# CoproMKII_Connectors.net
KiCad netlist of a schematic drawn in Altium Designer
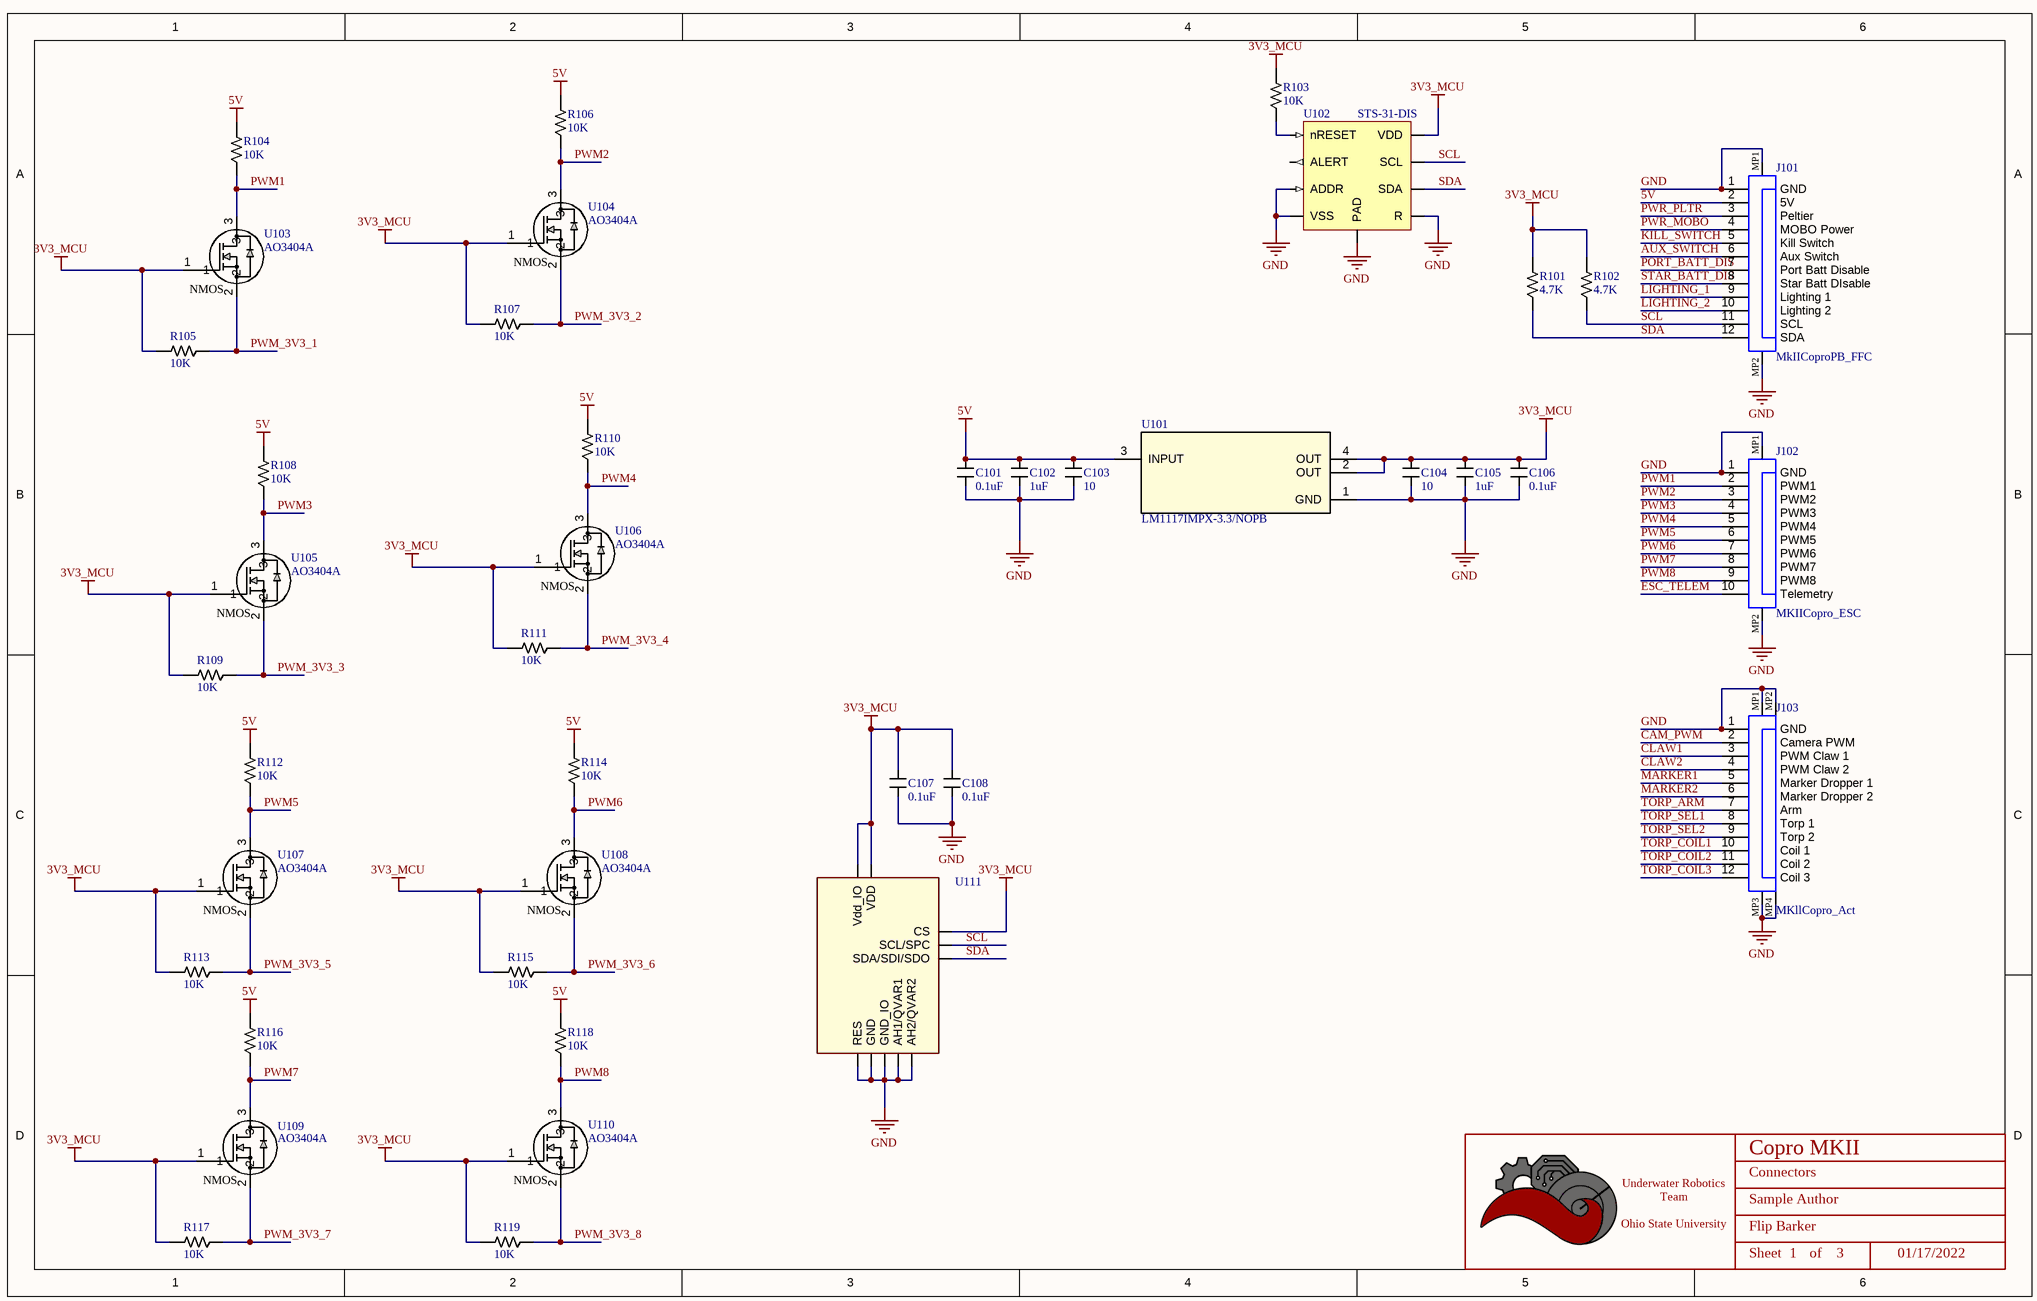
[diagram p0: CoproMKII_Connectors.SchDoc]

(export (version "E")
  (design (tool "Eeschema 10.0.6"))
  (components
    (comp (ref "C101")
      (value "0.1uF")
      (footprint "CAPACITOR_0603")
      (description "Cap 100nF 6.3V +/-10%\r\nCeramic 0603")
      (fields
        (field (name "TOLERANCE") "+/- 10%")
        (field (name "VOLTAGE") "6.3V")
        (field (name "MADE BY") "Flip B")
      )
      (libsource (lib "Capacitors") (part "CAPACITOR_0.1uF_0603"))
    )
    (comp (ref "C102")
      (value "1uF")
      (footprint "CAPACITOR_0603")
      (description "Cap 1uF 16V +/-10%\r\nCeramic 0603")
      (fields
        (field (name "TOLERANCE") "+/- 10%")
        (field (name "VOLTAGE") "16V")
        (field (name "MADE BY") "Flip B")
      )
      (libsource (lib "Capacitors") (part "CAPACITOR_1uF_0603"))
    )
    (comp (ref "C103")
      (value "10uF Ceramic 6.3V")
      (footprint "CAPACITOR_0603")
      (description "Cap 10uF 6.3V +/-20%\r\nCeramic 0603")
      (fields
        (field (name "TOLERANCE") "+/- 20%")
        (field (name "VOLTAGE") "6.3V")
        (field (name "VALUE (UF)") "10")
        (field (name "MADE BY") "Flip B")
      )
      (libsource (lib "Capacitors") (part "CAPACITOR_10uF_0603"))
    )
    (comp (ref "C104")
      (value "10uF Ceramic 6.3V")
      (footprint "CAPACITOR_0603")
      (description "Cap 10uF 6.3V +/-20%\r\nCeramic 0603")
      (fields
        (field (name "TOLERANCE") "+/- 20%")
        (field (name "VOLTAGE") "6.3V")
        (field (name "VALUE (UF)") "10")
        (field (name "MADE BY") "Flip B")
      )
      (libsource (lib "Capacitors") (part "CAPACITOR_10uF_0603"))
    )
    (comp (ref "C105")
      (value "1uF")
      (footprint "CAPACITOR_0603")
      (description "Cap 1uF 16V +/-10%\r\nCeramic 0603")
      (fields
        (field (name "TOLERANCE") "+/- 10%")
        (field (name "VOLTAGE") "16V")
        (field (name "MADE BY") "Flip B")
      )
      (libsource (lib "Capacitors") (part "CAPACITOR_1uF_0603"))
    )
    (comp (ref "C106")
      (value "0.1uF")
      (footprint "CAPACITOR_0603")
      (description "Cap 100nF 6.3V +/-10%\r\nCeramic 0603")
      (fields
        (field (name "TOLERANCE") "+/- 10%")
        (field (name "VOLTAGE") "6.3V")
        (field (name "MADE BY") "Flip B")
      )
      (libsource (lib "Capacitors") (part "CAPACITOR_0.1uF_0603"))
    )
    (comp (ref "C107")
      (value "0.1uF")
      (footprint "CAPACITOR_0603")
      (description "Cap 100nF 6.3V +/-10%\r\nCeramic 0603")
      (fields
        (field (name "TOLERANCE") "+/- 10%")
        (field (name "VOLTAGE") "6.3V")
        (field (name "MADE BY") "Flip B")
      )
      (libsource (lib "Capacitors") (part "CAPACITOR_0.1uF_0603"))
    )
    (comp (ref "C108")
      (value "0.1uF")
      (footprint "CAPACITOR_0603")
      (description "Cap 100nF 6.3V +/-10%\r\nCeramic 0603")
      (fields
        (field (name "TOLERANCE") "+/- 10%")
        (field (name "VOLTAGE") "6.3V")
        (field (name "MADE BY") "Flip B")
      )
      (libsource (lib "Capacitors") (part "CAPACITOR_0.1uF_0603"))
    )
    (comp (ref "J101")
      (value "MkIICoproPB_FFC")
      (footprint "68611214122")
      (description "WR-FPC SMT ZIF Horizontal Top Contact, pitch 1mm, 12p")
      (fields
        (field (name "MANUFACTURER PART NUMBER") "68611214122")
        (field (name "MANUFACTURER") "Wurth Elektronik")
      )
      (libsource (lib "Connectors") (part "MkIICoproPB_FFC"))
    )
    (comp (ref "J102")
      (value "MKIICopro_ESC")
      (footprint "68611014122")
      (description "WR-FPC SMT ZIF Horizontal Top Contact, pitch 1mm, 10p")
      (fields
        (field (name "MANUFACTURER PART NUMBER") "68611014122")
        (field (name "MANUFACTURER") "Wurth Elektronik")
      )
      (libsource (lib "Connectors") (part "MKIICopro_ESC"))
    )
    (comp (ref "J103")
      (value "MKllCopro_Act")
      (footprint "686112183822")
      (description "WR-FPC SMT ZIF Vertical Type A, pitch 1mm, 12p")
      (fields
        (field (name "MANUFACTURER PART NUMBER") "686112183822")
        (field (name "MANUFACTURER") "Wurth Elektronik")
      )
      (libsource (lib "Connectors") (part "MKllCopro_Act"))
    )
    (comp (ref "R101")
      (value "4.7k Ohm 5% 1/8W")
      (footprint "RESISTOR_0805")
      (description "RES 4.7k OHM 5% 1/8W 0805")
      (fields
        (field (name "TOLERANCE") "+/- 5%")
        (field (name "VALUE  (OHMS)") "4.7K")
        (field (name "MADE BY") "Robert Pafford")
      )
      (libsource (lib "Resistors") (part "RESISTOR_4.7K_0805"))
    )
    (comp (ref "R102")
      (value "4.7k Ohm 5% 1/8W")
      (footprint "RESISTOR_0805")
      (description "RES 4.7k OHM 5% 1/8W 0805")
      (fields
        (field (name "TOLERANCE") "+/- 5%")
        (field (name "VALUE  (OHMS)") "4.7K")
        (field (name "MADE BY") "Robert Pafford")
      )
      (libsource (lib "Resistors") (part "RESISTOR_4.7K_0805"))
    )
    (comp (ref "R103")
      (value "10k Ohm 5% 1/10W")
      (footprint "RESISTOR_0603")
      (description "RES 10k OHM 5% 1/10W 0603")
      (fields
        (field (name "TOLERANCE") "+/- 5%")
        (field (name "VALUE  (OHMS)") "10K")
        (field (name "MADE BY") "Robert Pafford")
      )
      (libsource (lib "Resistors") (part "RESISTOR_10K_0603"))
    )
    (comp (ref "R104")
      (value "10k Ohm 5% 1/10W")
      (footprint "RESISTOR_0603")
      (description "RES 10k OHM 5% 1/10W 0603")
      (fields
        (field (name "TOLERANCE") "+/- 5%")
        (field (name "VALUE  (OHMS)") "10K")
        (field (name "MADE BY") "Robert Pafford")
      )
      (libsource (lib "Resistors") (part "RESISTOR_10K_0603"))
    )
    (comp (ref "R105")
      (value "10k Ohm 5% 1/10W")
      (footprint "RESISTOR_0603")
      (description "RES 10k OHM 5% 1/10W 0603")
      (fields
        (field (name "TOLERANCE") "+/- 5%")
        (field (name "VALUE  (OHMS)") "10K")
        (field (name "MADE BY") "Robert Pafford")
      )
      (libsource (lib "Resistors") (part "RESISTOR_10K_0603"))
    )
    (comp (ref "R106")
      (value "10k Ohm 5% 1/10W")
      (footprint "RESISTOR_0603")
      (description "RES 10k OHM 5% 1/10W 0603")
      (fields
        (field (name "TOLERANCE") "+/- 5%")
        (field (name "VALUE  (OHMS)") "10K")
        (field (name "MADE BY") "Robert Pafford")
      )
      (libsource (lib "Resistors") (part "RESISTOR_10K_0603"))
    )
    (comp (ref "R107")
      (value "10k Ohm 5% 1/10W")
      (footprint "RESISTOR_0603")
      (description "RES 10k OHM 5% 1/10W 0603")
      (fields
        (field (name "TOLERANCE") "+/- 5%")
        (field (name "VALUE  (OHMS)") "10K")
        (field (name "MADE BY") "Robert Pafford")
      )
      (libsource (lib "Resistors") (part "RESISTOR_10K_0603"))
    )
    (comp (ref "R108")
      (value "10k Ohm 5% 1/10W")
      (footprint "RESISTOR_0603")
      (description "RES 10k OHM 5% 1/10W 0603")
      (fields
        (field (name "TOLERANCE") "+/- 5%")
        (field (name "VALUE  (OHMS)") "10K")
        (field (name "MADE BY") "Robert Pafford")
      )
      (libsource (lib "Resistors") (part "RESISTOR_10K_0603"))
    )
    (comp (ref "R109")
      (value "10k Ohm 5% 1/10W")
      (footprint "RESISTOR_0603")
      (description "RES 10k OHM 5% 1/10W 0603")
      (fields
        (field (name "TOLERANCE") "+/- 5%")
        (field (name "VALUE  (OHMS)") "10K")
        (field (name "MADE BY") "Robert Pafford")
      )
      (libsource (lib "Resistors") (part "RESISTOR_10K_0603"))
    )
    (comp (ref "R110")
      (value "10k Ohm 5% 1/10W")
      (footprint "RESISTOR_0603")
      (description "RES 10k OHM 5% 1/10W 0603")
      (fields
        (field (name "TOLERANCE") "+/- 5%")
        (field (name "VALUE  (OHMS)") "10K")
        (field (name "MADE BY") "Robert Pafford")
      )
      (libsource (lib "Resistors") (part "RESISTOR_10K_0603"))
    )
    (comp (ref "R111")
      (value "10k Ohm 5% 1/10W")
      (footprint "RESISTOR_0603")
      (description "RES 10k OHM 5% 1/10W 0603")
      (fields
        (field (name "TOLERANCE") "+/- 5%")
        (field (name "VALUE  (OHMS)") "10K")
        (field (name "MADE BY") "Robert Pafford")
      )
      (libsource (lib "Resistors") (part "RESISTOR_10K_0603"))
    )
    (comp (ref "R112")
      (value "10k Ohm 5% 1/10W")
      (footprint "RESISTOR_0603")
      (description "RES 10k OHM 5% 1/10W 0603")
      (fields
        (field (name "TOLERANCE") "+/- 5%")
        (field (name "VALUE  (OHMS)") "10K")
        (field (name "MADE BY") "Robert Pafford")
      )
      (libsource (lib "Resistors") (part "RESISTOR_10K_0603"))
    )
    (comp (ref "R113")
      (value "10k Ohm 5% 1/10W")
      (footprint "RESISTOR_0603")
      (description "RES 10k OHM 5% 1/10W 0603")
      (fields
        (field (name "TOLERANCE") "+/- 5%")
        (field (name "VALUE  (OHMS)") "10K")
        (field (name "MADE BY") "Robert Pafford")
      )
      (libsource (lib "Resistors") (part "RESISTOR_10K_0603"))
    )
    (comp (ref "R114")
      (value "10k Ohm 5% 1/10W")
      (footprint "RESISTOR_0603")
      (description "RES 10k OHM 5% 1/10W 0603")
      (fields
        (field (name "TOLERANCE") "+/- 5%")
        (field (name "VALUE  (OHMS)") "10K")
        (field (name "MADE BY") "Robert Pafford")
      )
      (libsource (lib "Resistors") (part "RESISTOR_10K_0603"))
    )
    (comp (ref "R115")
      (value "10k Ohm 5% 1/10W")
      (footprint "RESISTOR_0603")
      (description "RES 10k OHM 5% 1/10W 0603")
      (fields
        (field (name "TOLERANCE") "+/- 5%")
        (field (name "VALUE  (OHMS)") "10K")
        (field (name "MADE BY") "Robert Pafford")
      )
      (libsource (lib "Resistors") (part "RESISTOR_10K_0603"))
    )
    (comp (ref "R116")
      (value "10k Ohm 5% 1/10W")
      (footprint "RESISTOR_0603")
      (description "RES 10k OHM 5% 1/10W 0603")
      (fields
        (field (name "TOLERANCE") "+/- 5%")
        (field (name "VALUE  (OHMS)") "10K")
        (field (name "MADE BY") "Robert Pafford")
      )
      (libsource (lib "Resistors") (part "RESISTOR_10K_0603"))
    )
    (comp (ref "R117")
      (value "10k Ohm 5% 1/10W")
      (footprint "RESISTOR_0603")
      (description "RES 10k OHM 5% 1/10W 0603")
      (fields
        (field (name "TOLERANCE") "+/- 5%")
        (field (name "VALUE  (OHMS)") "10K")
        (field (name "MADE BY") "Robert Pafford")
      )
      (libsource (lib "Resistors") (part "RESISTOR_10K_0603"))
    )
    (comp (ref "R118")
      (value "10k Ohm 5% 1/10W")
      (footprint "RESISTOR_0603")
      (description "RES 10k OHM 5% 1/10W 0603")
      (fields
        (field (name "TOLERANCE") "+/- 5%")
        (field (name "VALUE  (OHMS)") "10K")
        (field (name "MADE BY") "Robert Pafford")
      )
      (libsource (lib "Resistors") (part "RESISTOR_10K_0603"))
    )
    (comp (ref "R119")
      (value "10k Ohm 5% 1/10W")
      (footprint "RESISTOR_0603")
      (description "RES 10k OHM 5% 1/10W 0603")
      (fields
        (field (name "TOLERANCE") "+/- 5%")
        (field (name "VALUE  (OHMS)") "10K")
        (field (name "MADE BY") "Robert Pafford")
      )
      (libsource (lib "Resistors") (part "RESISTOR_10K_0603"))
    )
    (comp (ref "U101")
      (value "LM1117IMPX-3.3/NOPB")
      (footprint "SOT-223-4")
      (description "IC REG LIN 3.3V 800MA SOT223-4")
      (fields
        (field (name "PARTNUMBER") "LM1117IMP-3.3/NOPB")
        (field (name "MANUFACTURER") "Texas Instruments")
        (field (name "CREATED BY") "Dylan T")
      )
      (libsource (lib "Converter") (part "LM1117IMPX-3.3/NOPB"))
    )
    (comp (ref "U102")
      (value "STS-31-DIS")
      (footprint "8-TDFN")
      (description "Temperature Sensor Digital, Local 0°C ~ 90°C 16 b 8-TDFN (2.5x2.5)")
      (fields (field (name "MADE BY") "Robert Pafford"))
      (libsource (lib "Integrated Circuits") (part "STS-31-DIS"))
    )
    (comp (ref "U103")
      (value "AO3404A")
      (footprint "SOT-23-3")
      (description "N-Channel 30 V 5.8A (Ta) 1.4W (Ta) Surface Mount SOT-23-3")
      (fields (field (name "CREATED BY") "Dylan T"))
      (libsource (lib "Transistors") (part "AO3404A"))
    )
    (comp (ref "U104")
      (value "AO3404A")
      (footprint "SOT-23-3")
      (description "N-Channel 30 V 5.8A (Ta) 1.4W (Ta) Surface Mount SOT-23-3")
      (fields (field (name "CREATED BY") "Dylan T"))
      (libsource (lib "Transistors") (part "AO3404A"))
    )
    (comp (ref "U105")
      (value "AO3404A")
      (footprint "SOT-23-3")
      (description "N-Channel 30 V 5.8A (Ta) 1.4W (Ta) Surface Mount SOT-23-3")
      (fields (field (name "CREATED BY") "Dylan T"))
      (libsource (lib "Transistors") (part "AO3404A"))
    )
    (comp (ref "U106")
      (value "AO3404A")
      (footprint "SOT-23-3")
      (description "N-Channel 30 V 5.8A (Ta) 1.4W (Ta) Surface Mount SOT-23-3")
      (fields (field (name "CREATED BY") "Dylan T"))
      (libsource (lib "Transistors") (part "AO3404A"))
    )
    (comp (ref "U107")
      (value "AO3404A")
      (footprint "SOT-23-3")
      (description "N-Channel 30 V 5.8A (Ta) 1.4W (Ta) Surface Mount SOT-23-3")
      (fields (field (name "CREATED BY") "Dylan T"))
      (libsource (lib "Transistors") (part "AO3404A"))
    )
    (comp (ref "U108")
      (value "AO3404A")
      (footprint "SOT-23-3")
      (description "N-Channel 30 V 5.8A (Ta) 1.4W (Ta) Surface Mount SOT-23-3")
      (fields (field (name "CREATED BY") "Dylan T"))
      (libsource (lib "Transistors") (part "AO3404A"))
    )
    (comp (ref "U109")
      (value "AO3404A")
      (footprint "SOT-23-3")
      (description "N-Channel 30 V 5.8A (Ta) 1.4W (Ta) Surface Mount SOT-23-3")
      (fields (field (name "CREATED BY") "Dylan T"))
      (libsource (lib "Transistors") (part "AO3404A"))
    )
    (comp (ref "U110")
      (value "AO3404A")
      (footprint "SOT-23-3")
      (description "N-Channel 30 V 5.8A (Ta) 1.4W (Ta) Surface Mount SOT-23-3")
      (fields (field (name "CREATED BY") "Dylan T"))
      (libsource (lib "Transistors") (part "AO3404A"))
    )
    (comp (ref "U111")
      (value "ILPS22QSTR")
      (footprint "LGA10R50P2X3_200X200X80")
      (libsource (lib "Integrated Circuits") (part "ILPS22QSTR"))
    )
  )
  (nets
    (net (code "1") (name "/AUX_SWITCH") (class "Default")
      (node (ref "J101") (pin "6") (pinfunction "Aux_Switch_6") (pintype "passive"))
    )
    (net (code "2") (name "/CAM_PWM") (class "Default")
      (node (ref "J103") (pin "2") (pinfunction "Camera_PWM_2") (pintype "passive"))
    )
    (net (code "3") (name "/CLAW1") (class "Default")
      (node (ref "J103") (pin "3") (pinfunction "PWM_Claw_1_3") (pintype "passive"))
    )
    (net (code "4") (name "/CLAW2") (class "Default")
      (node (ref "J103") (pin "4") (pinfunction "PWM_Claw_2_4") (pintype "passive"))
    )
    (net (code "5") (name "/ESC_TELEM") (class "Default")
      (node (ref "J102") (pin "10") (pinfunction "Telemetry_10") (pintype "passive"))
    )
    (net (code "6") (name "/KILL_SWITCH") (class "Default")
      (node (ref "J101") (pin "5") (pinfunction "Kill_Switch_5") (pintype "passive"))
    )
    (net (code "7") (name "/LIGHTING_1") (class "Default")
      (node (ref "J101") (pin "9") (pinfunction "Lighting_1_9") (pintype "passive"))
    )
    (net (code "8") (name "/LIGHTING_2") (class "Default")
      (node (ref "J101") (pin "10") (pinfunction "Lighting_2_10") (pintype "passive"))
    )
    (net (code "9") (name "/MARKER1") (class "Default")
      (node (ref "J103") (pin "5") (pinfunction "Marker_Dropper_1_5") (pintype "passive"))
    )
    (net (code "10") (name "/MARKER2") (class "Default")
      (node (ref "J103") (pin "6") (pinfunction "Marker_Dropper_2_6") (pintype "passive"))
    )
    (net (code "11") (name "/PORT_BATT_DIS") (class "Default")
      (node (ref "J101") (pin "7") (pinfunction "Port_Batt_Disable_7") (pintype "passive"))
    )
    (net (code "12") (name "/PWM1") (class "Default")
      (node (ref "J102") (pin "2") (pinfunction "PWM1_2") (pintype "passive"))
      (node (ref "R104") (pin "2") (pinfunction "2_2") (pintype "passive"))
      (node (ref "U103") (pin "3") (pinfunction "3_3") (pintype "passive"))
    )
    (net (code "13") (name "/PWM2") (class "Default")
      (node (ref "J102") (pin "3") (pinfunction "PWM2_3") (pintype "passive"))
      (node (ref "R106") (pin "2") (pinfunction "2_2") (pintype "passive"))
      (node (ref "U104") (pin "3") (pinfunction "3_3") (pintype "passive"))
    )
    (net (code "14") (name "/PWM3") (class "Default")
      (node (ref "J102") (pin "4") (pinfunction "PWM3_4") (pintype "passive"))
      (node (ref "R108") (pin "2") (pinfunction "2_2") (pintype "passive"))
      (node (ref "U105") (pin "3") (pinfunction "3_3") (pintype "passive"))
    )
    (net (code "15") (name "/PWM4") (class "Default")
      (node (ref "J102") (pin "5") (pinfunction "PWM4_5") (pintype "passive"))
      (node (ref "R110") (pin "2") (pinfunction "2_2") (pintype "passive"))
      (node (ref "U106") (pin "3") (pinfunction "3_3") (pintype "passive"))
    )
    (net (code "16") (name "/PWM5") (class "Default")
      (node (ref "J102") (pin "6") (pinfunction "PWM5_6") (pintype "passive"))
      (node (ref "R112") (pin "2") (pinfunction "2_2") (pintype "passive"))
      (node (ref "U107") (pin "3") (pinfunction "3_3") (pintype "passive"))
    )
    (net (code "17") (name "/PWM6") (class "Default")
      (node (ref "J102") (pin "7") (pinfunction "PWM6_7") (pintype "passive"))
      (node (ref "R114") (pin "2") (pinfunction "2_2") (pintype "passive"))
      (node (ref "U108") (pin "3") (pinfunction "3_3") (pintype "passive"))
    )
    (net (code "18") (name "/PWM7") (class "Default")
      (node (ref "J102") (pin "8") (pinfunction "PWM7_8") (pintype "passive"))
      (node (ref "R116") (pin "2") (pinfunction "2_2") (pintype "passive"))
      (node (ref "U109") (pin "3") (pinfunction "3_3") (pintype "passive"))
    )
    (net (code "19") (name "/PWM8") (class "Default")
      (node (ref "J102") (pin "9") (pinfunction "PWM8_9") (pintype "passive"))
      (node (ref "R118") (pin "2") (pinfunction "2_2") (pintype "passive"))
      (node (ref "U110") (pin "3") (pinfunction "3_3") (pintype "passive"))
    )
    (net (code "20") (name "/PWM_3V3_1") (class "Default")
      (node (ref "R105") (pin "2") (pinfunction "2_2") (pintype "passive"))
      (node (ref "U103") (pin "2") (pinfunction "2_2") (pintype "passive"))
    )
    (net (code "21") (name "/PWM_3V3_2") (class "Default")
      (node (ref "R107") (pin "2") (pinfunction "2_2") (pintype "passive"))
      (node (ref "U104") (pin "2") (pinfunction "2_2") (pintype "passive"))
    )
    (net (code "22") (name "/PWM_3V3_3") (class "Default")
      (node (ref "R109") (pin "2") (pinfunction "2_2") (pintype "passive"))
      (node (ref "U105") (pin "2") (pinfunction "2_2") (pintype "passive"))
    )
    (net (code "23") (name "/PWM_3V3_4") (class "Default")
      (node (ref "R111") (pin "2") (pinfunction "2_2") (pintype "passive"))
      (node (ref "U106") (pin "2") (pinfunction "2_2") (pintype "passive"))
    )
    (net (code "24") (name "/PWM_3V3_5") (class "Default")
      (node (ref "R113") (pin "2") (pinfunction "2_2") (pintype "passive"))
      (node (ref "U107") (pin "2") (pinfunction "2_2") (pintype "passive"))
    )
    (net (code "25") (name "/PWM_3V3_6") (class "Default")
      (node (ref "R115") (pin "2") (pinfunction "2_2") (pintype "passive"))
      (node (ref "U108") (pin "2") (pinfunction "2_2") (pintype "passive"))
    )
    (net (code "26") (name "/PWM_3V3_7") (class "Default")
      (node (ref "R117") (pin "2") (pinfunction "2_2") (pintype "passive"))
      (node (ref "U109") (pin "2") (pinfunction "2_2") (pintype "passive"))
    )
    (net (code "27") (name "/PWM_3V3_8") (class "Default")
      (node (ref "R119") (pin "2") (pinfunction "2_2") (pintype "passive"))
      (node (ref "U110") (pin "2") (pinfunction "2_2") (pintype "passive"))
    )
    (net (code "28") (name "/PWR_MOBO") (class "Default")
      (node (ref "J101") (pin "4") (pinfunction "MOBO_Power_4") (pintype "passive"))
    )
    (net (code "29") (name "/PWR_PLTR") (class "Default")
      (node (ref "J101") (pin "3") (pinfunction "Peltier_3") (pintype "passive"))
    )
    (net (code "30") (name "/SCL") (class "Default")
      (node (ref "J101") (pin "11") (pinfunction "SCL_11") (pintype "passive"))
      (node (ref "R102") (pin "2") (pinfunction "2_2") (pintype "passive"))
      (node (ref "U102") (pin "4") (pinfunction "SCL_4") (pintype "passive"))
      (node (ref "U111") (pin "2") (pinfunction "SCL/SPC_2") (pintype "passive"))
    )
    (net (code "31") (name "/SDA") (class "Default")
      (node (ref "J101") (pin "12") (pinfunction "SDA_12") (pintype "passive"))
      (node (ref "R101") (pin "2") (pinfunction "2_2") (pintype "passive"))
      (node (ref "U102") (pin "1") (pinfunction "SDA_1") (pintype "passive"))
      (node (ref "U111") (pin "4") (pinfunction "SDA/SDI/SDO_4") (pintype "passive"))
    )
    (net (code "32") (name "/STAR_BATT_DIS") (class "Default")
      (node (ref "J101") (pin "8") (pinfunction "Star_Batt_DIsable_8") (pintype "passive"))
    )
    (net (code "33") (name "/TORP_ARM") (class "Default")
      (node (ref "J103") (pin "7") (pinfunction "Arm_7") (pintype "passive"))
    )
    (net (code "34") (name "/TORP_COIL1") (class "Default")
      (node (ref "J103") (pin "10") (pinfunction "Coil_1_10") (pintype "passive"))
    )
    (net (code "35") (name "/TORP_COIL2") (class "Default")
      (node (ref "J103") (pin "11") (pinfunction "Coil_2_11") (pintype "passive"))
    )
    (net (code "36") (name "/TORP_COIL3") (class "Default")
      (node (ref "J103") (pin "12") (pinfunction "Coil_3_12") (pintype "passive"))
    )
    (net (code "37") (name "/TORP_SEL1") (class "Default")
      (node (ref "J103") (pin "8") (pinfunction "Torp_1_8") (pintype "passive"))
    )
    (net (code "38") (name "/TORP_SEL2") (class "Default")
      (node (ref "J103") (pin "9") (pinfunction "Torp_2_9") (pintype "passive"))
    )
    (net (code "39") (name "3V3_MCU") (class "Default")
      (node (ref "C104") (pin "1") (pinfunction "1_1") (pintype "passive"))
      (node (ref "C105") (pin "1") (pinfunction "1_1") (pintype "passive"))
      (node (ref "C106") (pin "1") (pinfunction "1_1") (pintype "passive"))
      (node (ref "C107") (pin "1") (pinfunction "1_1") (pintype "passive"))
      (node (ref "C108") (pin "1") (pinfunction "1_1") (pintype "passive"))
      (node (ref "R101") (pin "1") (pinfunction "1_1") (pintype "passive"))
      (node (ref "R102") (pin "1") (pinfunction "1_1") (pintype "passive"))
      (node (ref "R103") (pin "1") (pinfunction "1_1") (pintype "passive"))
      (node (ref "R105") (pin "1") (pinfunction "1_1") (pintype "passive"))
      (node (ref "R107") (pin "1") (pinfunction "1_1") (pintype "passive"))
      (node (ref "R109") (pin "1") (pinfunction "1_1") (pintype "passive"))
      (node (ref "R111") (pin "1") (pinfunction "1_1") (pintype "passive"))
      (node (ref "R113") (pin "1") (pinfunction "1_1") (pintype "passive"))
      (node (ref "R115") (pin "1") (pinfunction "1_1") (pintype "passive"))
      (node (ref "R117") (pin "1") (pinfunction "1_1") (pintype "passive"))
      (node (ref "R119") (pin "1") (pinfunction "1_1") (pintype "passive"))
      (node (ref "U101") (pin "2") (pinfunction "OUT_2") (pintype "power_in"))
      (node (ref "U101") (pin "4") (pinfunction "OUT_4") (pintype "power_in"))
      (node (ref "U102") (pin "5") (pinfunction "VDD_5") (pintype "power_in"))
      (node (ref "U103") (pin "1") (pinfunction "1_1") (pintype "passive"))
      (node (ref "U104") (pin "1") (pinfunction "1_1") (pintype "passive"))
      (node (ref "U105") (pin "1") (pinfunction "1_1") (pintype "passive"))
      (node (ref "U106") (pin "1") (pinfunction "1_1") (pintype "passive"))
      (node (ref "U107") (pin "1") (pinfunction "1_1") (pintype "passive"))
      (node (ref "U108") (pin "1") (pinfunction "1_1") (pintype "passive"))
      (node (ref "U109") (pin "1") (pinfunction "1_1") (pintype "passive"))
      (node (ref "U110") (pin "1") (pinfunction "1_1") (pintype "passive"))
      (node (ref "U111") (pin "1") (pinfunction "Vdd_IO_1") (pintype "passive"))
      (node (ref "U111") (pin "10") (pinfunction "VDD_10") (pintype "passive"))
      (node (ref "U111") (pin "6") (pinfunction "CS_6") (pintype "passive"))
    )
    (net (code "40") (name "5V") (class "Default")
      (node (ref "C101") (pin "1") (pinfunction "1_1") (pintype "passive"))
      (node (ref "C102") (pin "1") (pinfunction "1_1") (pintype "passive"))
      (node (ref "C103") (pin "1") (pinfunction "1_1") (pintype "passive"))
      (node (ref "J101") (pin "2") (pinfunction "5V_2") (pintype "passive"))
      (node (ref "R104") (pin "1") (pinfunction "1_1") (pintype "passive"))
      (node (ref "R106") (pin "1") (pinfunction "1_1") (pintype "passive"))
      (node (ref "R108") (pin "1") (pinfunction "1_1") (pintype "passive"))
      (node (ref "R110") (pin "1") (pinfunction "1_1") (pintype "passive"))
      (node (ref "R112") (pin "1") (pinfunction "1_1") (pintype "passive"))
      (node (ref "R114") (pin "1") (pinfunction "1_1") (pintype "passive"))
      (node (ref "R116") (pin "1") (pinfunction "1_1") (pintype "passive"))
      (node (ref "R118") (pin "1") (pinfunction "1_1") (pintype "passive"))
      (node (ref "U101") (pin "3") (pinfunction "INPUT_3") (pintype "power_in"))
    )
    (net (code "41") (name "GND") (class "Default")
      (node (ref "C101") (pin "2") (pinfunction "2_2") (pintype "passive"))
      (node (ref "C102") (pin "2") (pinfunction "2_2") (pintype "passive"))
      (node (ref "C103") (pin "2") (pinfunction "2_2") (pintype "passive"))
      (node (ref "C104") (pin "2") (pinfunction "2_2") (pintype "passive"))
      (node (ref "C105") (pin "2") (pinfunction "2_2") (pintype "passive"))
      (node (ref "C106") (pin "2") (pinfunction "2_2") (pintype "passive"))
      (node (ref "C107") (pin "2") (pinfunction "2_2") (pintype "passive"))
      (node (ref "C108") (pin "2") (pinfunction "2_2") (pintype "passive"))
      (node (ref "J101") (pin "1") (pinfunction "GND_1") (pintype "passive"))
      (node (ref "J101") (pin "MP1") (pinfunction "MP1_MP1") (pintype "passive"))
      (node (ref "J101") (pin "MP2") (pinfunction "MP2_MP2") (pintype "passive"))
      (node (ref "J102") (pin "1") (pinfunction "GND_1") (pintype "passive"))
      (node (ref "J102") (pin "MP1") (pinfunction "MP1_MP1") (pintype "passive"))
      (node (ref "J102") (pin "MP2") (pinfunction "MP2_MP2") (pintype "passive"))
      (node (ref "J103") (pin "1") (pinfunction "GND_1") (pintype "passive"))
      (node (ref "J103") (pin "MP1") (pinfunction "MP1_MP1") (pintype "passive"))
      (node (ref "J103") (pin "MP2") (pinfunction "MP2_MP2") (pintype "passive"))
      (node (ref "J103") (pin "MP3") (pinfunction "MP3_MP3") (pintype "passive"))
      (node (ref "J103") (pin "MP4") (pinfunction "MP4_MP4") (pintype "passive"))
      (node (ref "U101") (pin "1") (pinfunction "GND_1") (pintype "power_in"))
      (node (ref "U102") (pin "2") (pinfunction "ADDR_2") (pintype "input"))
      (node (ref "U102") (pin "7") (pinfunction "R_7") (pintype "passive"))
      (node (ref "U102") (pin "8") (pinfunction "VSS_8") (pintype "power_in"))
      (node (ref "U102") (pin "9") (pinfunction "PAD_9") (pintype "power_in"))
      (node (ref "U111") (pin "3") (pinfunction "RES_3") (pintype "passive"))
      (node (ref "U111") (pin "5") (pinfunction "AH2/QVAR2_5") (pintype "passive"))
      (node (ref "U111") (pin "7") (pinfunction "AH1/QVAR1_7") (pintype "passive"))
      (node (ref "U111") (pin "8") (pinfunction "GND_IO_8") (pintype "passive"))
      (node (ref "U111") (pin "9") (pinfunction "GND_9") (pintype "passive"))
    )
    (net (code "42") (name "Net-(U102-nRESET)") (class "Default")
      (node (ref "R103") (pin "2") (pinfunction "2_2") (pintype "passive"))
      (node (ref "U102") (pin "6") (pinfunction "nRESET_6") (pintype "input"))
    )
    (net (code "43") (name "unconnected-(U102-ALERT-Pad3)") (class "Default")
      (node (ref "U102") (pin "3") (pinfunction "ALERT_3") (pintype "output"))
    )
  )
)
